# dv_mcu_mpi_driver.net
KiCad netlist of a schematic drawn in Altium Designer
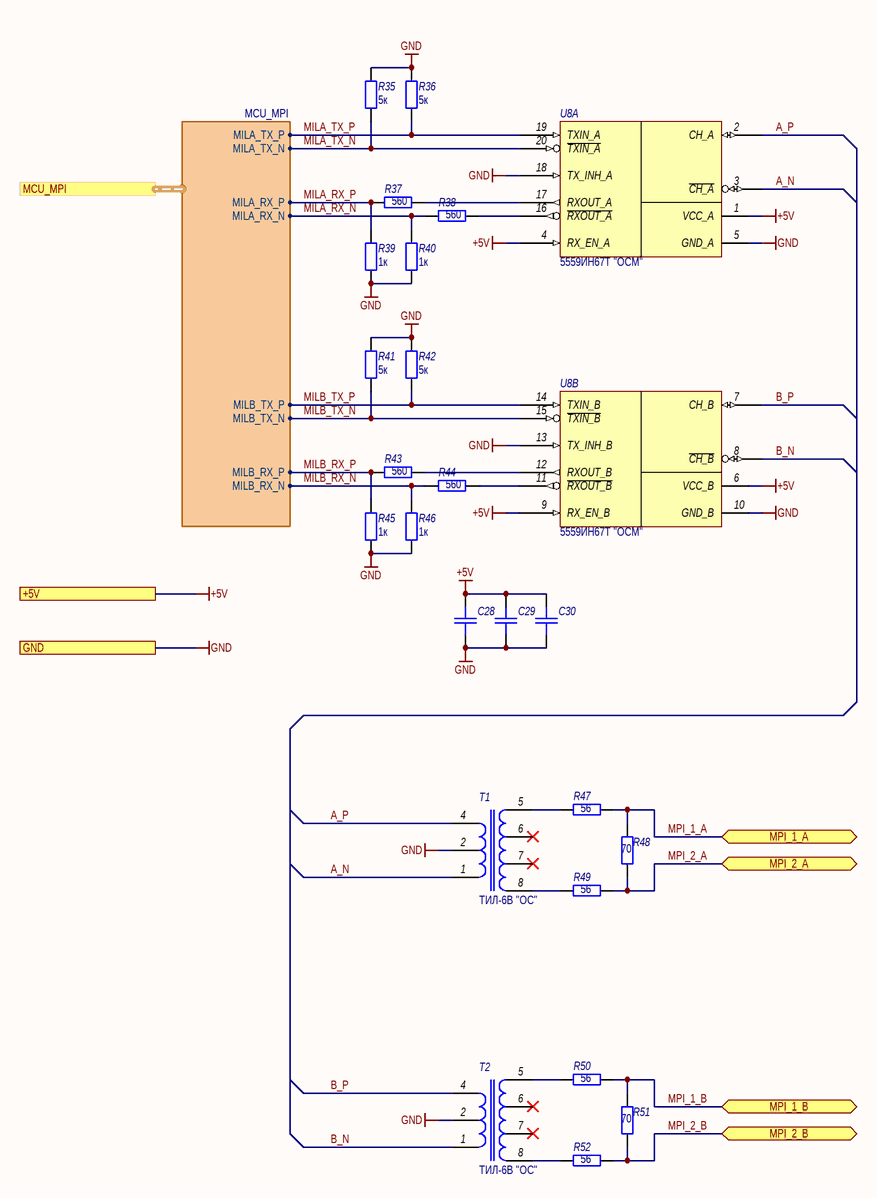
[diagram p0: dv_mcu_mpi_driver.SchDoc]

(export (version "E")
  (design (tool "Eeschema 10.0.6"))
  (components
    (comp (ref "C28")
      (value "K10-79")
      (footprint "SMD_C0805")
      (description "Capacitor")
      (libsource (lib "Passive") (part "Capacitor"))
    )
    (comp (ref "C29")
      (value "K10-79")
      (footprint "SMD_C0805")
      (description "Capacitor")
      (libsource (lib "Passive") (part "Capacitor"))
    )
    (comp (ref "C30")
      (value "K10-79")
      (footprint "SMD_C0805")
      (description "Capacitor")
      (libsource (lib "Passive") (part "Capacitor"))
    )
    (comp (ref "R35")
      (value "5к")
      (footprint "SMD_0805")
      (description "Resistor")
      (fields (field (name "Comment") "SMD_0805"))
      (libsource (lib "") (part "Resistor_1"))
    )
    (comp (ref "R36")
      (value "5к")
      (footprint "SMD_0805")
      (description "Resistor")
      (fields (field (name "Comment") "OSM R1-12"))
      (libsource (lib "") (part "Resistor_1"))
    )
    (comp (ref "R37")
      (value "560")
      (footprint "SMD_0805")
      (description "Resistor")
      (fields (field (name "Comment") "OSM R1-12"))
      (libsource (lib "Passive") (part "Resistor"))
    )
    (comp (ref "R38")
      (value "560")
      (footprint "SMD_0805")
      (description "Resistor")
      (fields (field (name "Comment") "OSM R1-12"))
      (libsource (lib "Passive") (part "Resistor"))
    )
    (comp (ref "R39")
      (value "1к")
      (footprint "SMD_0805")
      (description "Resistor")
      (fields (field (name "Comment") "OSM R1-12"))
      (libsource (lib "") (part "Resistor_1"))
    )
    (comp (ref "R40")
      (value "1к")
      (footprint "SMD_0805")
      (description "Resistor")
      (fields (field (name "Comment") "OSM R1-12"))
      (libsource (lib "") (part "Resistor_1"))
    )
    (comp (ref "R41")
      (value "5к")
      (footprint "SMD_0805")
      (description "Resistor")
      (fields (field (name "Comment") "OSM R1-12"))
      (libsource (lib "") (part "Resistor_1"))
    )
    (comp (ref "R42")
      (value "5к")
      (footprint "SMD_0805")
      (description "Resistor")
      (fields (field (name "Comment") "OSM R1-12"))
      (libsource (lib "") (part "Resistor_1"))
    )
    (comp (ref "R43")
      (value "560")
      (footprint "SMD_0805")
      (description "Resistor")
      (fields (field (name "Comment") "OSM R1-12"))
      (libsource (lib "Passive") (part "Resistor"))
    )
    (comp (ref "R44")
      (value "560")
      (footprint "SMD_0805")
      (description "Resistor")
      (fields (field (name "Comment") "OSM R1-12"))
      (libsource (lib "Passive") (part "Resistor"))
    )
    (comp (ref "R45")
      (value "1к")
      (footprint "SMD_0805")
      (description "Resistor")
      (fields (field (name "Comment") "OSM R1-12"))
      (libsource (lib "") (part "Resistor_1"))
    )
    (comp (ref "R46")
      (value "1к")
      (footprint "SMD_0805")
      (description "Resistor")
      (fields (field (name "Comment") "OSM R1-12"))
      (libsource (lib "") (part "Resistor_1"))
    )
    (comp (ref "R47")
      (value "56")
      (footprint "SMD_0805")
      (description "Resistor")
      (fields (field (name "Comment") "OSM R1-12"))
      (libsource (lib "") (part "Resistor_2"))
    )
    (comp (ref "R48")
      (value "70")
      (footprint "SMD_0805")
      (description "Resistor")
      (fields (field (name "Comment") "OSM R1-12"))
      (libsource (lib "") (part "Resistor_1"))
    )
    (comp (ref "R49")
      (value "56")
      (footprint "SMD_0805")
      (description "Resistor")
      (fields (field (name "Comment") "OSM R1-12"))
      (libsource (lib "") (part "Resistor_2"))
    )
    (comp (ref "R50")
      (value "56")
      (footprint "SMD_0805")
      (description "Resistor")
      (fields (field (name "Comment") "OSM R1-12"))
      (libsource (lib "") (part "Resistor_2"))
    )
    (comp (ref "R51")
      (value "70")
      (footprint "SMD_0805")
      (description "Resistor")
      (fields (field (name "Comment") "OSM R1-12"))
      (libsource (lib "") (part "Resistor_1"))
    )
    (comp (ref "R52")
      (value "56")
      (footprint "SMD_0805")
      (description "Resistor")
      (fields (field (name "Comment") "OSM R1-12"))
      (libsource (lib "") (part "Resistor_2"))
    )
    (comp (ref "T1")
      (value "TIL-6V")
      (footprint "TIL-6V")
      (description "Импульсный трансформатор")
      (fields (field (name "НАИМЕНОВАНИЕ") "ТИЛ-6В \"ОС\""))
      (libsource (lib "TIL-6V") (part "TIL-6V"))
    )
    (comp (ref "T2")
      (value "TIL-6V")
      (footprint "TIL-6V")
      (description "Импульсный трансформатор")
      (fields (field (name "НАИМЕНОВАНИЕ") "ТИЛ-6В \"ОС\""))
      (libsource (lib "TIL-6V") (part "TIL-6V"))
    )
    (comp (ref "U8")
      (value "5559IN67T_OSM")
      (footprint "4153.20-6")
      (description "Приемопередатчики манчестерского кода")
      (fields (field (name "НАИМЕНОВАНИЕ") "5559ИН67Т \"ОСМ\""))
      (libsource (lib "5559IN67T OSM") (part "5559IN67T"))
    )
  )
  (nets
    (net (code "2") (name "+5V") (class "Default")
      (node (ref "C28") (pin "2") (pinfunction "2_2") (pintype "passive"))
      (node (ref "C29") (pin "2") (pinfunction "2_2") (pintype "passive"))
      (node (ref "C30") (pin "2") (pinfunction "2_2") (pintype "passive"))
      (node (ref "U8") (pin "1") (pinfunction "VCC_A_1") (pintype "power_in"))
      (node (ref "U8") (pin "4") (pinfunction "RX_EN_A_4") (pintype "input"))
      (node (ref "U8") (pin "6") (pinfunction "VCC_B_6") (pintype "power_in"))
      (node (ref "U8") (pin "9") (pinfunction "RX_EN_B_9") (pintype "input"))
    )
    (net (code "3") (name "/A_N") (class "Default")
      (node (ref "T1") (pin "1") (pinfunction "1_1") (pintype "passive"))
      (node (ref "U8") (pin "3") (pinfunction "~{CH_A}_3") (pintype "bidirectional"))
    )
    (net (code "4") (name "/A_P") (class "Default")
      (node (ref "T1") (pin "4") (pinfunction "4_4") (pintype "passive"))
      (node (ref "U8") (pin "2") (pinfunction "CH_A_2") (pintype "bidirectional"))
    )
    (net (code "5") (name "/B_N") (class "Default")
      (node (ref "T2") (pin "1") (pinfunction "1_1") (pintype "passive"))
      (node (ref "U8") (pin "8") (pinfunction "~{CH_B}_8") (pintype "bidirectional"))
    )
    (net (code "6") (name "/B_P") (class "Default")
      (node (ref "T2") (pin "4") (pinfunction "4_4") (pintype "passive"))
      (node (ref "U8") (pin "7") (pinfunction "CH_B_7") (pintype "bidirectional"))
    )
    (net (code "7") (name "/MILA_RX_N") (class "Default")
      (node (ref "R38") (pin "1") (pinfunction "1_1") (pintype "passive"))
      (node (ref "R40") (pin "1") (pinfunction "1_1") (pintype "passive"))
    )
    (net (code "8") (name "/MILA_RX_P") (class "Default")
      (node (ref "R37") (pin "1") (pinfunction "1_1") (pintype "passive"))
      (node (ref "R39") (pin "1") (pinfunction "1_1") (pintype "passive"))
    )
    (net (code "9") (name "/MILA_TX_N") (class "Default")
      (node (ref "R35") (pin "2") (pinfunction "2_2") (pintype "passive"))
      (node (ref "U8") (pin "20") (pinfunction "~{TXIN_A}_20") (pintype "input"))
    )
    (net (code "10") (name "/MILA_TX_P") (class "Default")
      (node (ref "R36") (pin "2") (pinfunction "2_2") (pintype "passive"))
      (node (ref "U8") (pin "19") (pinfunction "TXIN_A_19") (pintype "input"))
    )
    (net (code "11") (name "/MILB_RX_N") (class "Default")
      (node (ref "R44") (pin "1") (pinfunction "1_1") (pintype "passive"))
      (node (ref "R46") (pin "1") (pinfunction "1_1") (pintype "passive"))
    )
    (net (code "12") (name "/MILB_RX_P") (class "Default")
      (node (ref "R43") (pin "1") (pinfunction "1_1") (pintype "passive"))
      (node (ref "R45") (pin "1") (pinfunction "1_1") (pintype "passive"))
    )
    (net (code "13") (name "/MILB_TX_N") (class "Default")
      (node (ref "R41") (pin "2") (pinfunction "2_2") (pintype "passive"))
      (node (ref "U8") (pin "15") (pinfunction "~{TXIN_B}_15") (pintype "input"))
    )
    (net (code "14") (name "/MILB_TX_P") (class "Default")
      (node (ref "R42") (pin "2") (pinfunction "2_2") (pintype "passive"))
      (node (ref "U8") (pin "14") (pinfunction "TXIN_B_14") (pintype "input"))
    )
    (net (code "15") (name "/MPI_1_A") (class "Default")
      (node (ref "R47") (pin "1") (pinfunction "1_1") (pintype "passive"))
      (node (ref "R48") (pin "1") (pinfunction "1_1") (pintype "passive"))
    )
    (net (code "16") (name "/MPI_1_B") (class "Default")
      (node (ref "R50") (pin "1") (pinfunction "1_1") (pintype "passive"))
      (node (ref "R51") (pin "1") (pinfunction "1_1") (pintype "passive"))
    )
    (net (code "17") (name "/MPI_2_A") (class "Default")
      (node (ref "R48") (pin "2") (pinfunction "2_2") (pintype "passive"))
      (node (ref "R49") (pin "1") (pinfunction "1_1") (pintype "passive"))
    )
    (net (code "18") (name "/MPI_2_B") (class "Default")
      (node (ref "R51") (pin "2") (pinfunction "2_2") (pintype "passive"))
      (node (ref "R52") (pin "1") (pinfunction "1_1") (pintype "passive"))
    )
    (net (code "20") (name "GND") (class "Default")
      (node (ref "C28") (pin "1") (pinfunction "1_1") (pintype "passive"))
      (node (ref "C29") (pin "1") (pinfunction "1_1") (pintype "passive"))
      (node (ref "C30") (pin "1") (pinfunction "1_1") (pintype "passive"))
      (node (ref "R35") (pin "1") (pinfunction "1_1") (pintype "passive"))
      (node (ref "R36") (pin "1") (pinfunction "1_1") (pintype "passive"))
      (node (ref "R39") (pin "2") (pinfunction "2_2") (pintype "passive"))
      (node (ref "R40") (pin "2") (pinfunction "2_2") (pintype "passive"))
      (node (ref "R41") (pin "1") (pinfunction "1_1") (pintype "passive"))
      (node (ref "R42") (pin "1") (pinfunction "1_1") (pintype "passive"))
      (node (ref "R45") (pin "2") (pinfunction "2_2") (pintype "passive"))
      (node (ref "R46") (pin "2") (pinfunction "2_2") (pintype "passive"))
      (node (ref "T1") (pin "2") (pinfunction "2_2") (pintype "passive"))
      (node (ref "T2") (pin "2") (pinfunction "2_2") (pintype "passive"))
      (node (ref "U8") (pin "10") (pinfunction "GND_B_10") (pintype "power_in"))
      (node (ref "U8") (pin "13") (pinfunction "TX_INH_B_13") (pintype "input"))
      (node (ref "U8") (pin "18") (pinfunction "TX_INH_A_18") (pintype "input"))
      (node (ref "U8") (pin "5") (pinfunction "GND_A_5") (pintype "power_in"))
    )
    (net (code "21") (name "Net-(R47-Pad2)") (class "Default")
      (node (ref "R47") (pin "2") (pinfunction "2_2") (pintype "passive"))
      (node (ref "T1") (pin "5") (pinfunction "5_5") (pintype "passive"))
    )
    (net (code "22") (name "Net-(R49-Pad2)") (class "Default")
      (node (ref "R49") (pin "2") (pinfunction "2_2") (pintype "passive"))
      (node (ref "T1") (pin "8") (pinfunction "8_8") (pintype "passive"))
    )
    (net (code "23") (name "Net-(R50-Pad2)") (class "Default")
      (node (ref "R50") (pin "2") (pinfunction "2_2") (pintype "passive"))
      (node (ref "T2") (pin "5") (pinfunction "5_5") (pintype "passive"))
    )
    (net (code "24") (name "Net-(R52-Pad2)") (class "Default")
      (node (ref "R52") (pin "2") (pinfunction "2_2") (pintype "passive"))
      (node (ref "T2") (pin "8") (pinfunction "8_8") (pintype "passive"))
    )
    (net (code "25") (name "Net-(U8A-RXOUT_A)") (class "Default")
      (node (ref "R37") (pin "2") (pinfunction "2_2") (pintype "passive"))
      (node (ref "U8") (pin "17") (pinfunction "RXOUT_A_17") (pintype "output"))
    )
    (net (code "26") (name "Net-(U8A-~{RXOUT_A})") (class "Default")
      (node (ref "R38") (pin "2") (pinfunction "2_2") (pintype "passive"))
      (node (ref "U8") (pin "16") (pinfunction "~{RXOUT_A}_16") (pintype "output"))
    )
    (net (code "27") (name "Net-(U8B-RXOUT_B)") (class "Default")
      (node (ref "R43") (pin "2") (pinfunction "2_2") (pintype "passive"))
      (node (ref "U8") (pin "12") (pinfunction "RXOUT_B_12") (pintype "output"))
    )
    (net (code "28") (name "Net-(U8B-~{RXOUT_B})") (class "Default")
      (node (ref "R44") (pin "2") (pinfunction "2_2") (pintype "passive"))
      (node (ref "U8") (pin "11") (pinfunction "~{RXOUT_B}_11") (pintype "output"))
    )
    (net (code "29") (name "unconnected-(T1-Pad6)") (class "Default")
      (node (ref "T1") (pin "6") (pinfunction "6_6") (pintype "passive+no_connect"))
    )
    (net (code "30") (name "unconnected-(T1-Pad7)") (class "Default")
      (node (ref "T1") (pin "7") (pinfunction "7_7") (pintype "passive+no_connect"))
    )
    (net (code "31") (name "unconnected-(T2-Pad6)") (class "Default")
      (node (ref "T2") (pin "6") (pinfunction "6_6") (pintype "passive+no_connect"))
    )
    (net (code "32") (name "unconnected-(T2-Pad7)") (class "Default")
      (node (ref "T2") (pin "7") (pinfunction "7_7") (pintype "passive+no_connect"))
    )
  )
)
